# um3567.net
KiCad netlist of a schematic drawn in EAGLE
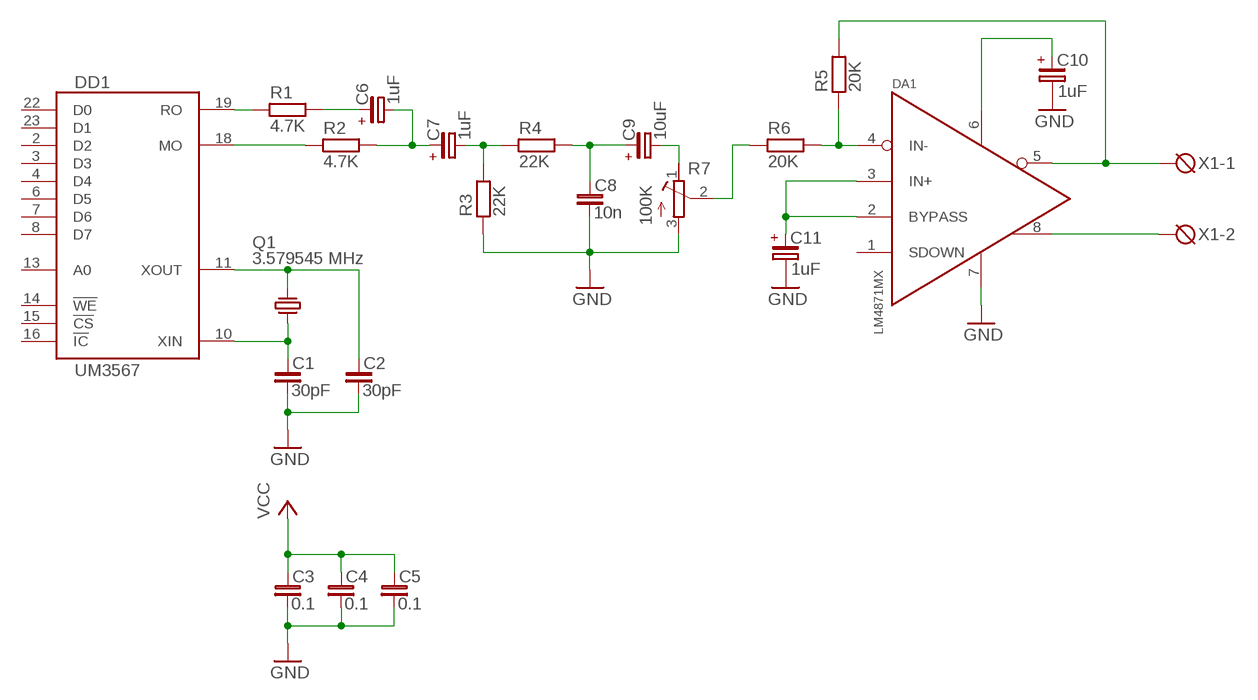
[diagram p0: schematic, sheet 1]

(export (version "E")
  (design (tool "Eeschema 10.0.6"))
  (components
    (comp (ref "C1")
      (value "30pF")
      (footprint "eagle-import:C0805")
      (libsource (lib "eagle-import") (part "C_0805"))
    )
    (comp (ref "C2")
      (value "30pF")
      (footprint "eagle-import:C0805")
      (libsource (lib "eagle-import") (part "C_0805"))
    )
    (comp (ref "C3")
      (value "0.1")
      (footprint "eagle-import:C0805")
      (libsource (lib "eagle-import") (part "C_0805"))
    )
    (comp (ref "C4")
      (value "0.1")
      (footprint "eagle-import:C0805")
      (libsource (lib "eagle-import") (part "C_0805"))
    )
    (comp (ref "C5")
      (value "0.1")
      (footprint "eagle-import:C0805")
      (libsource (lib "eagle-import") (part "C_0805"))
    )
    (comp (ref "C6")
      (value "1uF")
      (footprint "eagle-import:SMC_A")
      (libsource (lib "eagle-import") (part "CP_SMCA"))
    )
    (comp (ref "C7")
      (value "1uF")
      (footprint "eagle-import:SMC_A")
      (libsource (lib "eagle-import") (part "CP_SMCA"))
    )
    (comp (ref "C8")
      (value "10n")
      (footprint "eagle-import:C0805")
      (libsource (lib "eagle-import") (part "C_0805"))
    )
    (comp (ref "C9")
      (value "10uF")
      (footprint "eagle-import:SMC_A")
      (libsource (lib "eagle-import") (part "CP_SMCA"))
    )
    (comp (ref "C10")
      (value "1uF")
      (footprint "eagle-import:SMC_A")
      (libsource (lib "eagle-import") (part "CP_SMCA"))
    )
    (comp (ref "C11")
      (value "1uF")
      (footprint "eagle-import:SMC_A")
      (libsource (lib "eagle-import") (part "CP_SMCA"))
    )
    (comp (ref "DA1")
      (value "LM4871MX")
      (footprint "eagle-import:SO08")
      (libsource (lib "eagle-import") (part "LM4871MX"))
    )
    (comp (ref "DD1")
      (value "UM3567")
      (footprint "eagle-import:DIL24")
      (libsource (lib "eagle-import") (part "UM3567"))
    )
    (comp (ref "Q1")
      (value "3.579545 MHz")
      (footprint "eagle-import:HC49_S")
      (libsource (lib "eagle-import") (part "CRYSTAL-HC49S"))
    )
    (comp (ref "R1")
      (value "4.7K")
      (footprint "eagle-import:R0805")
      (libsource (lib "eagle-import") (part "R_0805"))
    )
    (comp (ref "R2")
      (value "4.7K")
      (footprint "eagle-import:R0805")
      (libsource (lib "eagle-import") (part "R_0805"))
    )
    (comp (ref "R3")
      (value "22K")
      (footprint "eagle-import:R0805")
      (libsource (lib "eagle-import") (part "R_0805"))
    )
    (comp (ref "R4")
      (value "22K")
      (footprint "eagle-import:R0805")
      (libsource (lib "eagle-import") (part "R_0805"))
    )
    (comp (ref "R5")
      (value "20K")
      (footprint "eagle-import:R0805")
      (libsource (lib "eagle-import") (part "R_0805"))
    )
    (comp (ref "R6")
      (value "20K")
      (footprint "eagle-import:R0805")
      (libsource (lib "eagle-import") (part "R_0805"))
    )
    (comp (ref "R7")
      (value "100K")
      (footprint "eagle-import:RTRIM-3362P")
      (libsource (lib "eagle-import") (part "RTRIM"))
    )
    (comp (ref "X1")
      (value "DG3XX-02-3.5")
      (footprint "eagle-import:DG350-3.5-02P")
      (libsource (lib "eagle-import") (part "DG3XX-02-3.5"))
    )
  )
  (nets
    (net (code "1") (name "GND") (class "Default")
      (node (ref "C1") (pin "2") (pinfunction "2_2") (pintype "passive"))
      (node (ref "C10") (pin "-") (pinfunction "-_-") (pintype "passive"))
      (node (ref "C11") (pin "-") (pinfunction "-_-") (pintype "passive"))
      (node (ref "C2") (pin "2") (pinfunction "2_2") (pintype "passive"))
      (node (ref "C3") (pin "2") (pinfunction "2_2") (pintype "passive"))
      (node (ref "C4") (pin "2") (pinfunction "2_2") (pintype "passive"))
      (node (ref "C5") (pin "2") (pinfunction "2_2") (pintype "passive"))
      (node (ref "C8") (pin "2") (pinfunction "2_2") (pintype "passive"))
      (node (ref "DA1") (pin "7") (pinfunction "GND_7") (pintype "power_in"))
      (node (ref "R3") (pin "1") (pinfunction "1_1") (pintype "passive"))
      (node (ref "R7") (pin "3") (pinfunction "E_3") (pintype "passive"))
    )
    (net (code "2") (name "Net-(C6-Pad+)") (class "Default")
      (node (ref "C6") (pin "+") (pinfunction "+_+") (pintype "passive"))
      (node (ref "R1") (pin "2") (pinfunction "2_2") (pintype "passive"))
    )
    (net (code "3") (name "Net-(C6-Pad-)") (class "Default")
      (node (ref "C6") (pin "-") (pinfunction "-_-") (pintype "passive"))
      (node (ref "C7") (pin "+") (pinfunction "+_+") (pintype "passive"))
      (node (ref "R2") (pin "2") (pinfunction "2_2") (pintype "passive"))
    )
    (net (code "4") (name "Net-(C7-Pad-)") (class "Default")
      (node (ref "C7") (pin "-") (pinfunction "-_-") (pintype "passive"))
      (node (ref "R3") (pin "2") (pinfunction "2_2") (pintype "passive"))
      (node (ref "R4") (pin "1") (pinfunction "1_1") (pintype "passive"))
    )
    (net (code "5") (name "Net-(C8-Pad1)") (class "Default")
      (node (ref "C8") (pin "1") (pinfunction "1_1") (pintype "passive"))
      (node (ref "C9") (pin "+") (pinfunction "+_+") (pintype "passive"))
      (node (ref "R4") (pin "2") (pinfunction "2_2") (pintype "passive"))
    )
    (net (code "6") (name "Net-(DA1-BYPASS)") (class "Default")
      (node (ref "C11") (pin "+") (pinfunction "+_+") (pintype "passive"))
      (node (ref "DA1") (pin "2") (pinfunction "BYPASS_2") (pintype "input"))
      (node (ref "DA1") (pin "3") (pinfunction "IN+_3") (pintype "input"))
    )
    (net (code "7") (name "Net-(DA1-IN-)") (class "Default")
      (node (ref "DA1") (pin "4") (pinfunction "IN-_4") (pintype "input"))
      (node (ref "R5") (pin "1") (pinfunction "1_1") (pintype "passive"))
      (node (ref "R6") (pin "2") (pinfunction "2_2") (pintype "passive"))
    )
    (net (code "8") (name "Net-(DA1-OUT+)") (class "Default")
      (node (ref "DA1") (pin "8") (pinfunction "OUT+_8") (pintype "output"))
      (node (ref "X1") (pin "2") (pinfunction "KL_2") (pintype "passive"))
    )
    (net (code "9") (name "Net-(DA1-OUT-)") (class "Default")
      (node (ref "DA1") (pin "5") (pinfunction "OUT-_5") (pintype "output"))
      (node (ref "R5") (pin "2") (pinfunction "2_2") (pintype "passive"))
      (node (ref "X1") (pin "1") (pinfunction "KL_1") (pintype "passive"))
    )
    (net (code "10") (name "Net-(DA1-VCC)") (class "Default")
      (node (ref "C10") (pin "+") (pinfunction "+_+") (pintype "passive"))
      (node (ref "DA1") (pin "6") (pinfunction "VCC_6") (pintype "power_in"))
    )
    (net (code "11") (name "Net-(DD1A-MO)") (class "Default")
      (node (ref "DD1") (pin "18") (pinfunction "MO_18") (pintype "output"))
      (node (ref "R2") (pin "1") (pinfunction "1_1") (pintype "passive"))
    )
    (net (code "12") (name "Net-(DD1A-RO)") (class "Default")
      (node (ref "DD1") (pin "19") (pinfunction "RO_19") (pintype "output"))
      (node (ref "R1") (pin "1") (pinfunction "1_1") (pintype "passive"))
    )
    (net (code "13") (name "Net-(DD1A-XIN)") (class "Default")
      (node (ref "C1") (pin "1") (pinfunction "1_1") (pintype "passive"))
      (node (ref "DD1") (pin "10") (pinfunction "XIN_10") (pintype "input"))
      (node (ref "Q1") (pin "1") (pinfunction "1_1") (pintype "passive"))
    )
    (net (code "14") (name "Net-(DD1A-XOUT)") (class "Default")
      (node (ref "C2") (pin "1") (pinfunction "1_1") (pintype "passive"))
      (node (ref "DD1") (pin "11") (pinfunction "XOUT_11") (pintype "output"))
      (node (ref "Q1") (pin "2") (pinfunction "2_2") (pintype "passive"))
    )
    (net (code "15") (name "Net-(R7-A)") (class "Default")
      (node (ref "C9") (pin "-") (pinfunction "-_-") (pintype "passive"))
      (node (ref "R7") (pin "1") (pinfunction "A_1") (pintype "passive"))
    )
    (net (code "16") (name "Net-(R7-S)") (class "Default")
      (node (ref "R6") (pin "1") (pinfunction "1_1") (pintype "passive"))
      (node (ref "R7") (pin "2") (pinfunction "S_2") (pintype "passive"))
    )
    (net (code "17") (name "VCC") (class "Default")
      (node (ref "C3") (pin "1") (pinfunction "1_1") (pintype "passive"))
      (node (ref "C4") (pin "1") (pinfunction "1_1") (pintype "passive"))
      (node (ref "C5") (pin "1") (pinfunction "1_1") (pintype "passive"))
    )
    (net (code "18") (name "unconnected-(DA1-SDOWN-Pad1)") (class "Default")
      (node (ref "DA1") (pin "1") (pinfunction "SDOWN_1") (pintype "input"))
    )
    (net (code "19") (name "unconnected-(DD1A-A0-Pad13)") (class "Default")
      (node (ref "DD1") (pin "13") (pinfunction "A0_13") (pintype "input"))
    )
    (net (code "20") (name "unconnected-(DD1A-D0-Pad22)") (class "Default")
      (node (ref "DD1") (pin "22") (pinfunction "D0_22") (pintype "bidirectional"))
    )
    (net (code "21") (name "unconnected-(DD1A-D1-Pad23)") (class "Default")
      (node (ref "DD1") (pin "23") (pinfunction "D1_23") (pintype "bidirectional"))
    )
    (net (code "22") (name "unconnected-(DD1A-D2-Pad2)") (class "Default")
      (node (ref "DD1") (pin "2") (pinfunction "D2_2") (pintype "bidirectional"))
    )
    (net (code "23") (name "unconnected-(DD1A-D3-Pad3)") (class "Default")
      (node (ref "DD1") (pin "3") (pinfunction "D3_3") (pintype "bidirectional"))
    )
    (net (code "24") (name "unconnected-(DD1A-D4-Pad4)") (class "Default")
      (node (ref "DD1") (pin "4") (pinfunction "D4_4") (pintype "bidirectional"))
    )
    (net (code "25") (name "unconnected-(DD1A-D5-Pad6)") (class "Default")
      (node (ref "DD1") (pin "6") (pinfunction "D5_6") (pintype "bidirectional"))
    )
    (net (code "26") (name "unconnected-(DD1A-D6-Pad7)") (class "Default")
      (node (ref "DD1") (pin "7") (pinfunction "D6_7") (pintype "bidirectional"))
    )
    (net (code "27") (name "unconnected-(DD1A-D7-Pad8)") (class "Default")
      (node (ref "DD1") (pin "8") (pinfunction "D7_8") (pintype "bidirectional"))
    )
    (net (code "28") (name "unconnected-(DD1A-~{CS}-Pad15)") (class "Default")
      (node (ref "DD1") (pin "15") (pinfunction "~{CS}_15") (pintype "input"))
    )
    (net (code "29") (name "unconnected-(DD1A-~{IC}-Pad16)") (class "Default")
      (node (ref "DD1") (pin "16") (pinfunction "~{IC}_16") (pintype "input"))
    )
    (net (code "30") (name "unconnected-(DD1A-~{WE}-Pad14)") (class "Default")
      (node (ref "DD1") (pin "14") (pinfunction "~{WE}_14") (pintype "input"))
    )
  )
)
